# ArduinoUNO_shield.net
KiCad netlist of a schematic drawn in EAGLE
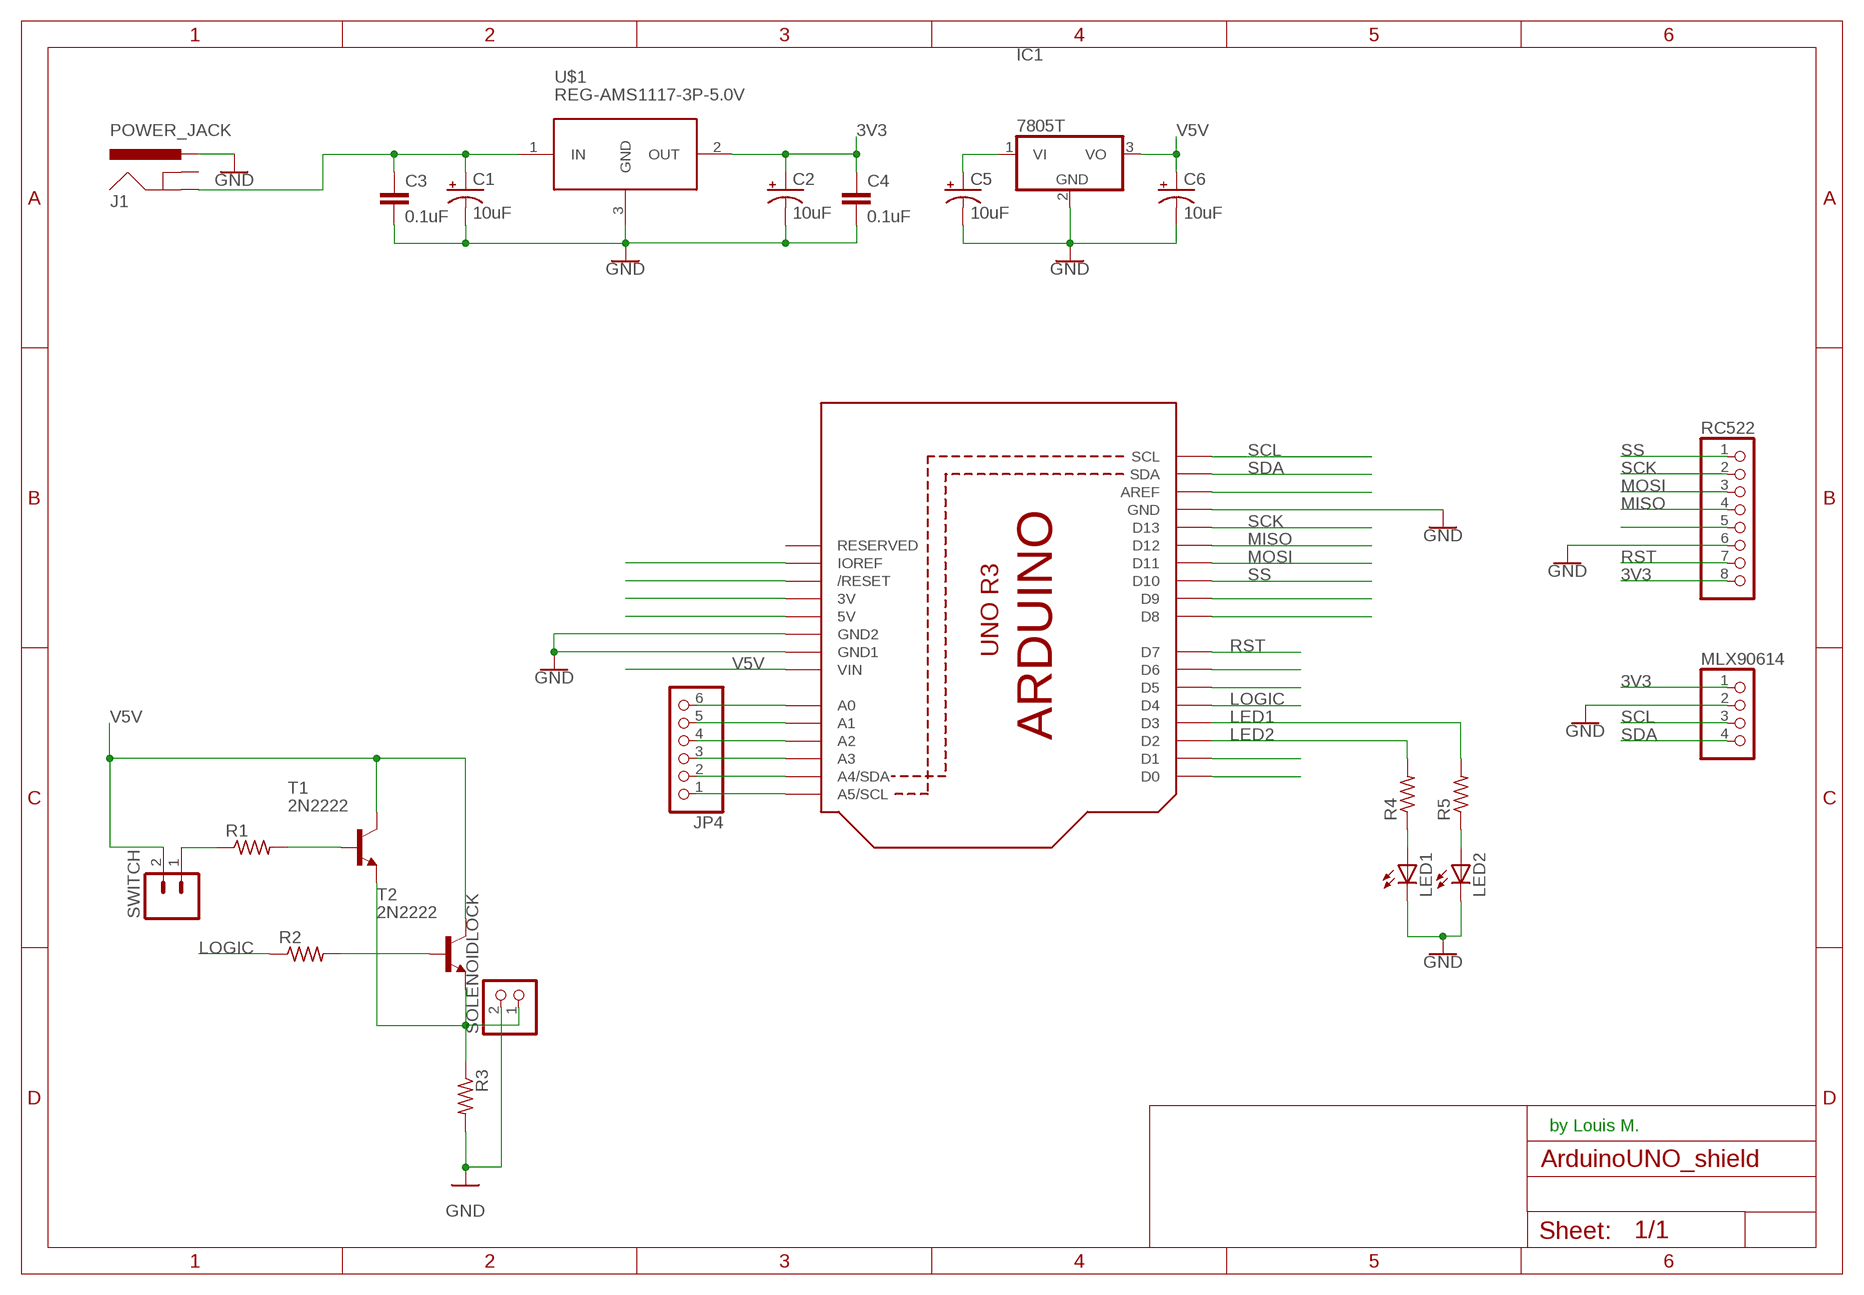
[diagram p0: schematic, sheet 1]

(export (version "E")
  (design (tool "Eeschema 10.0.6"))
  (components
    (comp (ref "C1")
      (value "10uF")
      (footprint "eagle-import:CPOL-RADIAL-2.5MM-5MM-KIT")
      (libsource (lib "eagle-import") (part "10UF-POLAR-RADIAL-2.5MM-KIT-25V-20%"))
    )
    (comp (ref "C2")
      (value "10uF")
      (footprint "eagle-import:CPOL-RADIAL-2.5MM-5MM-KIT")
      (libsource (lib "eagle-import") (part "10UF-POLAR-RADIAL-2.5MM-KIT-25V-20%"))
    )
    (comp (ref "C3")
      (value "0.1uF")
      (footprint "eagle-import:CAP-PTH-SMALL-KIT")
      (libsource (lib "eagle-import") (part "0.1UF-KIT-EZ-50V-20%"))
    )
    (comp (ref "C4")
      (value "0.1uF")
      (footprint "eagle-import:CAP-PTH-SMALL-KIT")
      (libsource (lib "eagle-import") (part "0.1UF-KIT-EZ-50V-20%"))
    )
    (comp (ref "C5")
      (value "10uF")
      (footprint "eagle-import:CPOL-RADIAL-2.5MM-5MM")
      (libsource (lib "eagle-import") (part "10UF-POLAR-RADIAL-2.5MM-25V-20%"))
    )
    (comp (ref "C6")
      (value "10uF")
      (footprint "eagle-import:CPOL-RADIAL-2.5MM-5MM")
      (libsource (lib "eagle-import") (part "10UF-POLAR-RADIAL-2.5MM-25V-20%"))
    )
    (comp (ref "IC1")
      (value "7805T")
      (footprint "eagle-import:TO220H")
      (libsource (lib "eagle-import") (part "78T05"))
    )
    (comp (ref "J1")
      (value "POWER_JACK")
      (footprint "eagle-import:POWER_JACK_PTH")
      (libsource (lib "eagle-import") (part "POWER_JACK"))
    )
    (comp (ref "JP4")
      (value "PINHD-1X6B")
      (footprint "eagle-import:1X06-BIG")
      (libsource (lib "eagle-import") (part "PINHD-1X6B"))
    )
    (comp (ref "LED1")
      (value "LED5MM")
      (footprint "eagle-import:LED5MM")
      (libsource (lib "eagle-import") (part "LED5MM"))
    )
    (comp (ref "LED2")
      (value "LED5MM")
      (footprint "eagle-import:LED5MM")
      (libsource (lib "eagle-import") (part "LED5MM"))
    )
    (comp (ref "MLX90614")
      (value "PINHD-1X4")
      (footprint "eagle-import:1X04")
      (libsource (lib "eagle-import") (part "PINHD-1X4"))
    )
    (comp (ref "R1")
      (value "R-US_0207/10")
      (footprint "eagle-import:0207_10")
      (libsource (lib "eagle-import") (part "R-US_0207/10"))
    )
    (comp (ref "R2")
      (value "R-US_0207/10")
      (footprint "eagle-import:0207_10")
      (libsource (lib "eagle-import") (part "R-US_0207/10"))
    )
    (comp (ref "R3")
      (value "R-US_0207/10")
      (footprint "eagle-import:0207_10")
      (libsource (lib "eagle-import") (part "R-US_0207/10"))
    )
    (comp (ref "R4")
      (value "R-US_0204/5")
      (footprint "eagle-import:0204_5")
      (libsource (lib "eagle-import") (part "R-US_0204/5"))
    )
    (comp (ref "R5")
      (value "R-US_0204/5")
      (footprint "eagle-import:0204_5")
      (libsource (lib "eagle-import") (part "R-US_0204/5"))
    )
    (comp (ref "RC522")
      (value "PINHD-1X8")
      (footprint "eagle-import:1X08")
      (libsource (lib "eagle-import") (part "PINHD-1X8"))
    )
    (comp (ref "SOLENOIDLOCK")
      (value "JST_2PIN-THM-RA")
      (footprint "eagle-import:JST-PH-2-THM-RA")
      (libsource (lib "eagle-import") (part "JST_2PIN-THM-RA"))
    )
    (comp (ref "SWITCH")
      (value "M02")
      (footprint "eagle-import:02P")
      (libsource (lib "eagle-import") (part "M02"))
    )
    (comp (ref "T1")
      (value "2N2222")
      (footprint "eagle-import:TO92-EBC-OVAL")
      (libsource (lib "eagle-import") (part "2N2222"))
    )
    (comp (ref "T2")
      (value "2N2222")
      (footprint "eagle-import:TO92-EBC-OVAL")
      (libsource (lib "eagle-import") (part "2N2222"))
    )
    (comp (ref "U$1")
      (value "REG-AMS1117-3P-5.0V")
      (footprint "eagle-import:REG-AMS1117-3P")
      (libsource (lib "eagle-import") (part "REG-AMS1117-3P-5.0V"))
    )
    (comp (ref "UNOR3")
      (value "ARDUINOR3-DIMENSION")
      (footprint "eagle-import:ARDUINOR3")
      (libsource (lib "eagle-import") (part "ARDUINOR3-DIMENSION"))
    )
  )
  (nets
    (net (code "1") (name "/3V3") (class "Default")
      (node (ref "C2") (pin "1") (pinfunction "+_1") (pintype "passive"))
      (node (ref "C4") (pin "1") (pinfunction "1_1") (pintype "passive"))
      (node (ref "MLX90614") (pin "1") (pinfunction "1_1") (pintype "passive"))
      (node (ref "RC522") (pin "8") (pinfunction "8_8") (pintype "passive"))
      (node (ref "U$1") (pin "2") (pinfunction "OUT_2") (pintype "bidirectional"))
    )
    (net (code "2") (name "/LED1") (class "Default")
      (node (ref "R5") (pin "2") (pinfunction "2_2") (pintype "passive"))
      (node (ref "UNOR3") (pin "D3") (pinfunction "D3_D3") (pintype "bidirectional"))
    )
    (net (code "3") (name "/LED2") (class "Default")
      (node (ref "R4") (pin "2") (pinfunction "2_2") (pintype "passive"))
      (node (ref "UNOR3") (pin "D2") (pinfunction "D2_D2") (pintype "bidirectional"))
    )
    (net (code "4") (name "/LOGIC") (class "Default")
      (node (ref "R2") (pin "1") (pinfunction "1_1") (pintype "passive"))
      (node (ref "UNOR3") (pin "D4") (pinfunction "D4_D4") (pintype "bidirectional"))
    )
    (net (code "5") (name "/MISO") (class "Default")
      (node (ref "RC522") (pin "4") (pinfunction "4_4") (pintype "passive"))
      (node (ref "UNOR3") (pin "D12") (pinfunction "D12_D12") (pintype "bidirectional"))
    )
    (net (code "6") (name "/MOSI") (class "Default")
      (node (ref "RC522") (pin "3") (pinfunction "3_3") (pintype "passive"))
      (node (ref "UNOR3") (pin "D11") (pinfunction "D11_D11") (pintype "bidirectional"))
    )
    (net (code "7") (name "/RST") (class "Default")
      (node (ref "RC522") (pin "7") (pinfunction "7_7") (pintype "passive"))
      (node (ref "UNOR3") (pin "D7") (pinfunction "D7_D7") (pintype "bidirectional"))
    )
    (net (code "8") (name "/SCK") (class "Default")
      (node (ref "RC522") (pin "2") (pinfunction "2_2") (pintype "passive"))
      (node (ref "UNOR3") (pin "D13") (pinfunction "D13_D13") (pintype "bidirectional"))
    )
    (net (code "9") (name "/SCL") (class "Default")
      (node (ref "MLX90614") (pin "3") (pinfunction "3_3") (pintype "passive"))
      (node (ref "UNOR3") (pin "SCL") (pinfunction "SCL_SCL") (pintype "bidirectional"))
    )
    (net (code "10") (name "/SDA") (class "Default")
      (node (ref "MLX90614") (pin "4") (pinfunction "4_4") (pintype "passive"))
      (node (ref "UNOR3") (pin "SDA") (pinfunction "SDA_SDA") (pintype "bidirectional"))
    )
    (net (code "11") (name "/SS") (class "Default")
      (node (ref "RC522") (pin "1") (pinfunction "1_1") (pintype "passive"))
      (node (ref "UNOR3") (pin "D10") (pinfunction "D10_D10") (pintype "bidirectional"))
    )
    (net (code "12") (name "/V5V") (class "Default")
      (node (ref "C6") (pin "1") (pinfunction "+_1") (pintype "passive"))
      (node (ref "IC1") (pin "3") (pinfunction "VO_3") (pintype "passive"))
      (node (ref "SWITCH") (pin "2") (pinfunction "2_2") (pintype "passive"))
      (node (ref "T1") (pin "C") (pinfunction "C_C") (pintype "passive"))
      (node (ref "T2") (pin "C") (pinfunction "C_C") (pintype "passive"))
      (node (ref "UNOR3") (pin "VIN") (pinfunction "VIN_VIN") (pintype "power_in"))
    )
    (net (code "13") (name "GND") (class "Default")
      (node (ref "C1") (pin "2") (pinfunction "-_2") (pintype "passive"))
      (node (ref "C2") (pin "2") (pinfunction "-_2") (pintype "passive"))
      (node (ref "C3") (pin "2") (pinfunction "2_2") (pintype "passive"))
      (node (ref "C4") (pin "2") (pinfunction "2_2") (pintype "passive"))
      (node (ref "C5") (pin "2") (pinfunction "-_2") (pintype "passive"))
      (node (ref "C6") (pin "2") (pinfunction "-_2") (pintype "passive"))
      (node (ref "IC1") (pin "2") (pinfunction "GND_2") (pintype "passive"))
      (node (ref "J1") (pin "PWR") (pinfunction "PWR_PWR") (pintype "bidirectional"))
      (node (ref "LED1") (pin "K") (pinfunction "C_K") (pintype "passive"))
      (node (ref "LED2") (pin "K") (pinfunction "C_K") (pintype "passive"))
      (node (ref "MLX90614") (pin "2") (pinfunction "2_2") (pintype "passive"))
      (node (ref "R3") (pin "2") (pinfunction "2_2") (pintype "passive"))
      (node (ref "RC522") (pin "6") (pinfunction "6_6") (pintype "passive"))
      (node (ref "SOLENOIDLOCK") (pin "2") (pinfunction "1_2") (pintype "passive"))
      (node (ref "U$1") (pin "3") (pinfunction "GND_3") (pintype "bidirectional"))
      (node (ref "UNOR3") (pin "GND") (pinfunction "GND_GND") (pintype "power_in"))
      (node (ref "UNOR3") (pin "GND1") (pinfunction "GND1_GND1") (pintype "power_in"))
      (node (ref "UNOR3") (pin "GND2") (pinfunction "GND2_GND2") (pintype "power_in"))
    )
    (net (code "14") (name "Net-(C1-+)") (class "Default")
      (node (ref "C1") (pin "1") (pinfunction "+_1") (pintype "passive"))
      (node (ref "C3") (pin "1") (pinfunction "1_1") (pintype "passive"))
      (node (ref "J1") (pin "GND") (pinfunction "GND_GND") (pintype "bidirectional"))
      (node (ref "U$1") (pin "1") (pinfunction "IN_1") (pintype "bidirectional"))
    )
    (net (code "15") (name "Net-(C5-+)") (class "Default")
      (node (ref "C5") (pin "1") (pinfunction "+_1") (pintype "passive"))
      (node (ref "IC1") (pin "1") (pinfunction "VI_1") (pintype "input"))
    )
    (net (code "16") (name "Net-(JP4-Pad3)") (class "Default")
      (node (ref "JP4") (pin "3") (pinfunction "3_3") (pintype "passive"))
      (node (ref "UNOR3") (pin "A3") (pinfunction "A3_A3") (pintype "bidirectional"))
    )
    (net (code "17") (name "Net-(JP4-Pad4)") (class "Default")
      (node (ref "JP4") (pin "4") (pinfunction "4_4") (pintype "passive"))
      (node (ref "UNOR3") (pin "A2") (pinfunction "A2_A2") (pintype "bidirectional"))
    )
    (net (code "18") (name "Net-(JP4-Pad5)") (class "Default")
      (node (ref "JP4") (pin "5") (pinfunction "5_5") (pintype "passive"))
      (node (ref "UNOR3") (pin "A1") (pinfunction "A1_A1") (pintype "bidirectional"))
    )
    (net (code "19") (name "Net-(JP4-Pad6)") (class "Default")
      (node (ref "JP4") (pin "6") (pinfunction "6_6") (pintype "passive"))
      (node (ref "UNOR3") (pin "A0") (pinfunction "A0_A0") (pintype "bidirectional"))
    )
    (net (code "20") (name "Net-(LED1-PadA)") (class "Default")
      (node (ref "LED1") (pin "A") (pinfunction "A_A") (pintype "passive"))
      (node (ref "R4") (pin "1") (pinfunction "1_1") (pintype "passive"))
    )
    (net (code "21") (name "Net-(LED2-PadA)") (class "Default")
      (node (ref "LED2") (pin "A") (pinfunction "A_A") (pintype "passive"))
      (node (ref "R5") (pin "1") (pinfunction "1_1") (pintype "passive"))
    )
    (net (code "22") (name "Net-(R1-Pad1)") (class "Default")
      (node (ref "R1") (pin "1") (pinfunction "1_1") (pintype "passive"))
      (node (ref "SWITCH") (pin "1") (pinfunction "1_1") (pintype "passive"))
    )
    (net (code "23") (name "Net-(R1-Pad2)") (class "Default")
      (node (ref "R1") (pin "2") (pinfunction "2_2") (pintype "passive"))
      (node (ref "T1") (pin "B") (pinfunction "B_B") (pintype "passive"))
    )
    (net (code "24") (name "Net-(R2-Pad2)") (class "Default")
      (node (ref "R2") (pin "2") (pinfunction "2_2") (pintype "passive"))
      (node (ref "T2") (pin "B") (pinfunction "B_B") (pintype "passive"))
    )
    (net (code "25") (name "Net-(SOLENOIDLOCK-2)") (class "Default")
      (node (ref "R3") (pin "1") (pinfunction "1_1") (pintype "passive"))
      (node (ref "SOLENOIDLOCK") (pin "1") (pinfunction "2_1") (pintype "passive"))
      (node (ref "T1") (pin "E") (pinfunction "E_E") (pintype "passive"))
      (node (ref "T2") (pin "E") (pinfunction "E_E") (pintype "passive"))
    )
    (net (code "26") (name "Net-(UNOR3-A4{slash}SDA)") (class "Default")
      (node (ref "JP4") (pin "2") (pinfunction "2_2") (pintype "passive"))
      (node (ref "UNOR3") (pin "A4") (pinfunction "A4/SDA_A4") (pintype "bidirectional"))
    )
    (net (code "27") (name "Net-(UNOR3-A5{slash}SCL)") (class "Default")
      (node (ref "JP4") (pin "1") (pinfunction "1_1") (pintype "passive"))
      (node (ref "UNOR3") (pin "A5") (pinfunction "A5/SCL_A5") (pintype "bidirectional"))
    )
    (net (code "28") (name "unconnected-(J1-PadGNDBREAK)") (class "Default")
      (node (ref "J1") (pin "GNDBREAK") (pinfunction "GNDBREAK_GNDBREAK") (pintype "bidirectional"))
    )
    (net (code "29") (name "unconnected-(RC522-Pad5)") (class "Default")
      (node (ref "RC522") (pin "5") (pinfunction "5_5") (pintype "passive"))
    )
    (net (code "30") (name "unconnected-(UNOR3-Pad3V)") (class "Default")
      (node (ref "UNOR3") (pin "3V") (pinfunction "3V_3V") (pintype "power_in"))
    )
    (net (code "31") (name "unconnected-(UNOR3-Pad5V)") (class "Default")
      (node (ref "UNOR3") (pin "5V") (pinfunction "5V_5V") (pintype "power_in"))
    )
    (net (code "32") (name "unconnected-(UNOR3-PadAREF)") (class "Default")
      (node (ref "UNOR3") (pin "AREF") (pinfunction "AREF_AREF") (pintype "bidirectional"))
    )
    (net (code "33") (name "unconnected-(UNOR3-PadD0)") (class "Default")
      (node (ref "UNOR3") (pin "D0") (pinfunction "D0_D0") (pintype "bidirectional"))
    )
    (net (code "34") (name "unconnected-(UNOR3-PadD1)") (class "Default")
      (node (ref "UNOR3") (pin "D1") (pinfunction "D1_D1") (pintype "bidirectional"))
    )
    (net (code "35") (name "unconnected-(UNOR3-PadD5)") (class "Default")
      (node (ref "UNOR3") (pin "D5") (pinfunction "D5_D5") (pintype "bidirectional"))
    )
    (net (code "36") (name "unconnected-(UNOR3-PadD6)") (class "Default")
      (node (ref "UNOR3") (pin "D6") (pinfunction "D6_D6") (pintype "bidirectional"))
    )
    (net (code "37") (name "unconnected-(UNOR3-PadD8)") (class "Default")
      (node (ref "UNOR3") (pin "D8") (pinfunction "D8_D8") (pintype "bidirectional"))
    )
    (net (code "38") (name "unconnected-(UNOR3-PadD9)") (class "Default")
      (node (ref "UNOR3") (pin "D9") (pinfunction "D9_D9") (pintype "bidirectional"))
    )
    (net (code "39") (name "unconnected-(UNOR3-PadIOREF)") (class "Default")
      (node (ref "UNOR3") (pin "IOREF") (pinfunction "IOREF_IOREF") (pintype "output"))
    )
    (net (code "40") (name "unconnected-(UNOR3-PadRESERVED)") (class "Default")
      (node (ref "UNOR3") (pin "RESERVED") (pinfunction "RESERVED_RESERVED") (pintype "no_connect"))
    )
    (net (code "41") (name "unconnected-(UNOR3-{slash}RESET-PadRESET)") (class "Default")
      (node (ref "UNOR3") (pin "RESET") (pinfunction "/RESET_RESET") (pintype "bidirectional"))
    )
  )
)
